# CW340_FTDI.net
KiCad netlist of a schematic drawn in Altium Designer
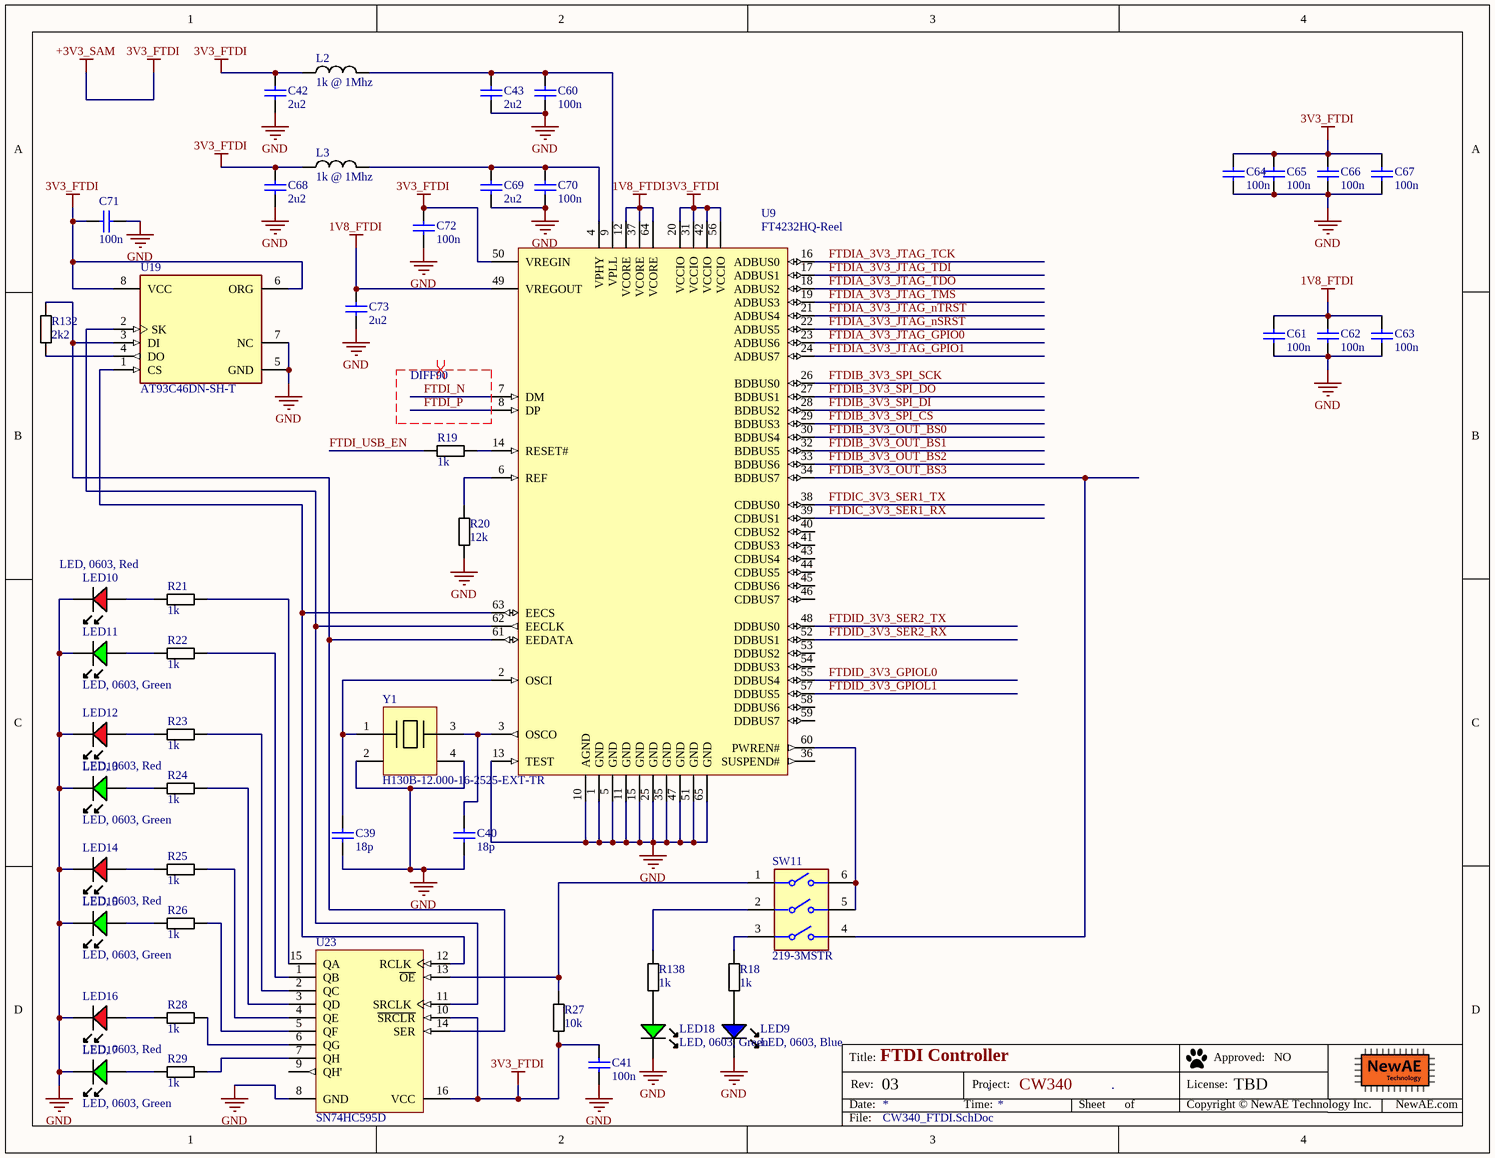
[diagram p0: CW340_FTDI.SchDoc]

(export (version "E")
  (design (tool "Eeschema 10.0.6"))
  (components
    (comp (ref "C39")
      (value "18p")
      (footprint "CAPC0402_M")
      (description "18p, 0402")
      (fields (field (name "PART NUMBER") "CCHIP-18p-0402"))
      (libsource (lib "NewAE_AltiumLib") (part "CAP"))
    )
    (comp (ref "C40")
      (value "18p")
      (footprint "CAPC0402_M")
      (description "18p, 0402")
      (fields (field (name "PART NUMBER") "CCHIP-18p-0402"))
      (libsource (lib "NewAE_AltiumLib") (part "CAP"))
    )
    (comp (ref "C41")
      (value "100n")
      (footprint "CAPC0402_M")
      (description "100n, 0402")
      (fields (field (name "PART NUMBER") "CCHIP-100n-0402"))
      (libsource (lib "NewAE_AltiumLib") (part "CAP"))
    )
    (comp (ref "C42")
      (value "2u2")
      (footprint "CAPC0603_M")
      (description "2u2, 0603")
      (fields (field (name "PART NUMBER") "CCHIP-2u2-0603"))
      (libsource (lib "NewAE_AltiumLib") (part "CAP"))
    )
    (comp (ref "C43")
      (value "2u2")
      (footprint "CAPC0603_M")
      (description "2u2, 0603")
      (fields (field (name "PART NUMBER") "CCHIP-2u2-0603"))
      (libsource (lib "NewAE_AltiumLib") (part "CAP"))
    )
    (comp (ref "C60")
      (value "100n")
      (footprint "CAPC0402_M")
      (description "100n, 0402")
      (fields (field (name "PART NUMBER") "CCHIP-100n-0402"))
      (libsource (lib "NewAE_AltiumLib") (part "CAP"))
    )
    (comp (ref "C61")
      (value "100n")
      (footprint "CAPC0402_M")
      (description "100n, 0402")
      (fields (field (name "PART NUMBER") "CCHIP-100n-0402"))
      (libsource (lib "NewAE_AltiumLib") (part "CAP"))
    )
    (comp (ref "C62")
      (value "100n")
      (footprint "CAPC0402_M")
      (description "100n, 0402")
      (fields (field (name "PART NUMBER") "CCHIP-100n-0402"))
      (libsource (lib "NewAE_AltiumLib") (part "CAP"))
    )
    (comp (ref "C63")
      (value "100n")
      (footprint "CAPC0402_M")
      (description "100n, 0402")
      (fields (field (name "PART NUMBER") "CCHIP-100n-0402"))
      (libsource (lib "NewAE_AltiumLib") (part "CAP"))
    )
    (comp (ref "C64")
      (value "100n")
      (footprint "CAPC0402_M")
      (description "100n, 0402")
      (fields (field (name "PART NUMBER") "CCHIP-100n-0402"))
      (libsource (lib "NewAE_AltiumLib") (part "CAP"))
    )
    (comp (ref "C65")
      (value "100n")
      (footprint "CAPC0402_M")
      (description "100n, 0402")
      (fields (field (name "PART NUMBER") "CCHIP-100n-0402"))
      (libsource (lib "NewAE_AltiumLib") (part "CAP"))
    )
    (comp (ref "C66")
      (value "100n")
      (footprint "CAPC0402_M")
      (description "100n, 0402")
      (fields (field (name "PART NUMBER") "CCHIP-100n-0402"))
      (libsource (lib "NewAE_AltiumLib") (part "CAP"))
    )
    (comp (ref "C67")
      (value "100n")
      (footprint "CAPC0402_M")
      (description "100n, 0402")
      (fields (field (name "PART NUMBER") "CCHIP-100n-0402"))
      (libsource (lib "NewAE_AltiumLib") (part "CAP"))
    )
    (comp (ref "C68")
      (value "2u2")
      (footprint "CAPC0603_M")
      (description "2u2, 0603")
      (fields (field (name "PART NUMBER") "CCHIP-2u2-0603"))
      (libsource (lib "NewAE_AltiumLib") (part "CAP"))
    )
    (comp (ref "C69")
      (value "2u2")
      (footprint "CAPC0603_M")
      (description "2u2, 0603")
      (fields (field (name "PART NUMBER") "CCHIP-2u2-0603"))
      (libsource (lib "NewAE_AltiumLib") (part "CAP"))
    )
    (comp (ref "C70")
      (value "100n")
      (footprint "CAPC0402_M")
      (description "100n, 0402")
      (fields (field (name "PART NUMBER") "CCHIP-100n-0402"))
      (libsource (lib "NewAE_AltiumLib") (part "CAP"))
    )
    (comp (ref "C71")
      (value "100n")
      (footprint "CAPC0402_M")
      (description "100n, 0402")
      (fields (field (name "PART NUMBER") "CCHIP-100n-0402"))
      (libsource (lib "NewAE_AltiumLib") (part "CAP"))
    )
    (comp (ref "C72")
      (value "100n")
      (footprint "CAPC0402_M")
      (description "100n, 0402")
      (fields (field (name "PART NUMBER") "CCHIP-100n-0402"))
      (libsource (lib "NewAE_AltiumLib") (part "CAP"))
    )
    (comp (ref "C73")
      (value "2u2")
      (footprint "CAPC0603_M")
      (description "2u2, 0603")
      (fields (field (name "PART NUMBER") "CCHIP-2u2-0603"))
      (libsource (lib "NewAE_AltiumLib") (part "CAP"))
    )
    (comp (ref "L2")
      (value "1k @ 1Mhz")
      (footprint "IND_0603")
      (description "Ferrite Beads HI CUR CHIP BD 0603 1000OHMS 25%")
      (fields (field (name "PART NUMBER") "FBCHIP-1k-0603"))
      (libsource (lib "NewAE_AltiumLib") (part "IND"))
    )
    (comp (ref "L3")
      (value "1k @ 1Mhz")
      (footprint "IND_0603")
      (description "Ferrite Beads HI CUR CHIP BD 0603 1000OHMS 25%")
      (fields (field (name "PART NUMBER") "FBCHIP-1k-0603"))
      (libsource (lib "NewAE_AltiumLib") (part "IND"))
    )
    (comp (ref "LED9")
      (value "LED, 0603, Blue")
      (footprint "LED-0603-BLUE")
      (description "Chip LED, Blue")
      (fields (field (name "PART NUMBER") "LEDCHIP_0603_BLUE"))
      (libsource (lib "NewAE_AltiumLib") (part "LED_BLUE"))
    )
    (comp (ref "LED10")
      (value "LED, 0603, Red")
      (footprint "LED-0603-RED")
      (description "Chip LED, Red")
      (fields (field (name "PART NUMBER") "LEDCHIP_0603_RED"))
      (libsource (lib "NewAE_AltiumLib") (part "LED_RED"))
    )
    (comp (ref "LED11")
      (value "LED, 0603, Green")
      (footprint "LED-0603-GREEN")
      (description "Chip LED, Green")
      (fields (field (name "PART NUMBER") "LEDCHIP_0603_GREEN"))
      (libsource (lib "NewAE_AltiumLib") (part "LED_GREEN"))
    )
    (comp (ref "LED12")
      (value "LED, 0603, Red")
      (footprint "LED-0603-RED")
      (description "Chip LED, Red")
      (fields (field (name "PART NUMBER") "LEDCHIP_0603_RED"))
      (libsource (lib "NewAE_AltiumLib") (part "LED_RED"))
    )
    (comp (ref "LED13")
      (value "LED, 0603, Green")
      (footprint "LED-0603-GREEN")
      (description "Chip LED, Green")
      (fields (field (name "PART NUMBER") "LEDCHIP_0603_GREEN"))
      (libsource (lib "NewAE_AltiumLib") (part "LED_GREEN"))
    )
    (comp (ref "LED14")
      (value "LED, 0603, Red")
      (footprint "LED-0603-RED")
      (description "Chip LED, Red")
      (fields (field (name "PART NUMBER") "LEDCHIP_0603_RED"))
      (libsource (lib "NewAE_AltiumLib") (part "LED_RED"))
    )
    (comp (ref "LED15")
      (value "LED, 0603, Green")
      (footprint "LED-0603-GREEN")
      (description "Chip LED, Green")
      (fields (field (name "PART NUMBER") "LEDCHIP_0603_GREEN"))
      (libsource (lib "NewAE_AltiumLib") (part "LED_GREEN"))
    )
    (comp (ref "LED16")
      (value "LED, 0603, Red")
      (footprint "LED-0603-RED")
      (description "Chip LED, Red")
      (fields (field (name "PART NUMBER") "LEDCHIP_0603_RED"))
      (libsource (lib "NewAE_AltiumLib") (part "LED_RED"))
    )
    (comp (ref "LED17")
      (value "LED, 0603, Green")
      (footprint "LED-0603-GREEN")
      (description "Chip LED, Green")
      (fields (field (name "PART NUMBER") "LEDCHIP_0603_GREEN"))
      (libsource (lib "NewAE_AltiumLib") (part "LED_GREEN"))
    )
    (comp (ref "LED18")
      (value "LED, 0603, Green")
      (footprint "LED-0603-GREEN")
      (description "Chip LED, Green")
      (fields (field (name "PART NUMBER") "LEDCHIP_0603_GREEN"))
      (libsource (lib "NewAE_AltiumLib") (part "LED_GREEN"))
    )
    (comp (ref "R18")
      (value "1k")
      (footprint "RESC1005X40N")
      (description "1k res, 0402, 1%, 1/16W")
      (fields (field (name "PART NUMBER") "RCHIP-1K-0402") (field (name "TOLERANCE") "1%"))
      (libsource (lib "") (part "RES-EU_1"))
    )
    (comp (ref "R19")
      (value "1k")
      (footprint "RESC1005X40N")
      (description "1k res, 0402, 1%, 1/16W")
      (fields (field (name "PART NUMBER") "RCHIP-1K-0402") (field (name "TOLERANCE") "1%"))
      (libsource (lib "NewAE_AltiumLib") (part "RES-EU"))
    )
    (comp (ref "R20")
      (value "12k")
      (footprint "RESC1608X55N")
      (description "12k res, 0603, 1%, 1/10W")
      (fields (field (name "PART NUMBER") "RCHIP-12K-0603") (field (name "TOLERANCE") "1%"))
      (libsource (lib "") (part "RES-EU_1"))
    )
    (comp (ref "R21")
      (value "1k")
      (footprint "RESC1005X40N")
      (description "1k res, 0402, 1%, 1/16W")
      (fields (field (name "PART NUMBER") "RCHIP-1K-0402") (field (name "TOLERANCE") "1%"))
      (libsource (lib "NewAE_AltiumLib") (part "RES-EU"))
    )
    (comp (ref "R22")
      (value "1k")
      (footprint "RESC1005X40N")
      (description "1k res, 0402, 1%, 1/16W")
      (fields (field (name "PART NUMBER") "RCHIP-1K-0402") (field (name "TOLERANCE") "1%"))
      (libsource (lib "NewAE_AltiumLib") (part "RES-EU"))
    )
    (comp (ref "R23")
      (value "1k")
      (footprint "RESC1005X40N")
      (description "1k res, 0402, 1%, 1/16W")
      (fields (field (name "PART NUMBER") "RCHIP-1K-0402") (field (name "TOLERANCE") "1%"))
      (libsource (lib "NewAE_AltiumLib") (part "RES-EU"))
    )
    (comp (ref "R24")
      (value "1k")
      (footprint "RESC1005X40N")
      (description "1k res, 0402, 1%, 1/16W")
      (fields (field (name "PART NUMBER") "RCHIP-1K-0402") (field (name "TOLERANCE") "1%"))
      (libsource (lib "NewAE_AltiumLib") (part "RES-EU"))
    )
    (comp (ref "R25")
      (value "1k")
      (footprint "RESC1005X40N")
      (description "1k res, 0402, 1%, 1/16W")
      (fields (field (name "PART NUMBER") "RCHIP-1K-0402") (field (name "TOLERANCE") "1%"))
      (libsource (lib "NewAE_AltiumLib") (part "RES-EU"))
    )
    (comp (ref "R26")
      (value "1k")
      (footprint "RESC1005X40N")
      (description "1k res, 0402, 1%, 1/16W")
      (fields (field (name "PART NUMBER") "RCHIP-1K-0402") (field (name "TOLERANCE") "1%"))
      (libsource (lib "NewAE_AltiumLib") (part "RES-EU"))
    )
    (comp (ref "R27")
      (value "10k")
      (footprint "RESC1005X40N")
      (description "10k res, 0402, 1%, 1/16W")
      (fields (field (name "PART NUMBER") "RCHIP-10K-0402") (field (name "TOLERANCE") "1%"))
      (libsource (lib "") (part "RES-EU_1"))
    )
    (comp (ref "R28")
      (value "1k")
      (footprint "RESC1005X40N")
      (description "1k res, 0402, 1%, 1/16W")
      (fields (field (name "PART NUMBER") "RCHIP-1K-0402") (field (name "TOLERANCE") "1%"))
      (libsource (lib "NewAE_AltiumLib") (part "RES-EU"))
    )
    (comp (ref "R29")
      (value "1k")
      (footprint "RESC1005X40N")
      (description "1k res, 0402, 1%, 1/16W")
      (fields (field (name "PART NUMBER") "RCHIP-1K-0402") (field (name "TOLERANCE") "1%"))
      (libsource (lib "NewAE_AltiumLib") (part "RES-EU"))
    )
    (comp (ref "R132")
      (value "2k2")
      (footprint "RESC1005X40N")
      (description "2k2 res, 0402, 1%, 1/16W")
      (fields (field (name "PART NUMBER") "RCHIP-2K2-0402") (field (name "TOLERANCE") "1%"))
      (libsource (lib "") (part "RES-EU_1"))
    )
    (comp (ref "R138")
      (value "1k")
      (footprint "RESC1005X40N")
      (description "1k res, 0402, 1%, 1/16W")
      (fields (field (name "PART NUMBER") "RCHIP-1K-0402") (field (name "TOLERANCE") "1%"))
      (libsource (lib "") (part "RES-EU_1"))
    )
    (comp (ref "SW11")
      (value "219-3MSTR")
      (footprint "FP-219-3MSTR-MFG")
      (description "SWITCH SLIDE DIP SPST 100MA 20V")
      (libsource (lib "Altium Content Vault") (part "7c490946f25aa2bb1cd4cef5bc3ec4e"))
    )
    (comp (ref "U9")
      (value "FT4232HQ-Reel")
      (footprint "QFN64_2_L")
      (description "Quad High Speed USB To Multipurpose UART/MPSSE IC, 64-pin QFN, Tape and Reel")
      (fields (field (name "MANUFACTURER") "FTDI"))
      (libsource (lib "Altium Content Vault") (part "COM-UART-FT4232H-QFN64"))
    )
    (comp (ref "U19")
      (value "AT93C46DN-SH-T")
      (footprint "FP-C04-057-SN-MFG")
      (description "IC EEPROM 1K SPI 2MHZ 8SOIC")
      (fields
        (field (name "MANUFACTURER") "Microchip")
        (field (name "OCTOPART") "https://octopart.com/at93c46dn-sh-t-microchip-77759177")
      )
      (libsource (lib "Altium Content Vault") (part "8bb9afc094b350e480db350c7247e52"))
    )
    (comp (ref "U23")
      (value "SN74HC595D")
      (footprint "D0016A_L")
      (description "8-Bit Shift Registers With 3-State Output Registers, D0016A, TUBE")
      (fields
        (field (name "GENERIC PART NUMBER") "SN74HC595")
        (field (name "MANUFACTURER") "Texas Instruments")
      )
      (libsource (lib "Altium Content Vault") (part "TI-SN74XHCT595X_SN74LV595A-16"))
    )
    (comp (ref "Y1")
      (value "H130B-12.000-16-2525-EXT-TR")
      (footprint "5x3.2MM XTAL")
      (description "12MHz ±25ppm Crystal 16pF 35 Ohms 4-SMD, No Lead")
      (fields (field (name "MANUFACTURER PART NUMBER") "H130B-12.000-16-2525-EXT-TR"))
      (libsource (lib "NewAE_AltiumLib") (part "H130B-12.000-16-2525-EXT-TR"))
    )
  )
  (nets
    (net (code "1") (name "+3V3_SAM") (class "Default")
      (node (ref "C41") (pin "1") (pinfunction "1_1") (pintype "passive"))
      (node (ref "C42") (pin "1") (pinfunction "1_1") (pintype "passive"))
      (node (ref "C64") (pin "1") (pinfunction "1_1") (pintype "passive"))
      (node (ref "C65") (pin "1") (pinfunction "1_1") (pintype "passive"))
      (node (ref "C66") (pin "1") (pinfunction "1_1") (pintype "passive"))
      (node (ref "C67") (pin "1") (pinfunction "1_1") (pintype "passive"))
      (node (ref "C68") (pin "1") (pinfunction "1_1") (pintype "passive"))
      (node (ref "C71") (pin "1") (pinfunction "1_1") (pintype "passive"))
      (node (ref "C72") (pin "1") (pinfunction "1_1") (pintype "passive"))
      (node (ref "L2") (pin "1") (pinfunction "1_1") (pintype "passive"))
      (node (ref "L3") (pin "1") (pinfunction "1_1") (pintype "passive"))
      (node (ref "R27") (pin "2") (pinfunction "2_2") (pintype "passive"))
      (node (ref "U19") (pin "6") (pinfunction "ORG_6") (pintype "passive"))
      (node (ref "U19") (pin "8") (pinfunction "VCC_8") (pintype "power_in"))
      (node (ref "U23") (pin "10") (pinfunction "~{SRCLR}_10") (pintype "input"))
      (node (ref "U23") (pin "16") (pinfunction "VCC_16") (pintype "power_in"))
      (node (ref "U9") (pin "20") (pinfunction "VCCIO_20") (pintype "power_in"))
      (node (ref "U9") (pin "31") (pinfunction "VCCIO_31") (pintype "power_in"))
      (node (ref "U9") (pin "42") (pinfunction "VCCIO_42") (pintype "power_in"))
      (node (ref "U9") (pin "50") (pinfunction "VREGIN_50") (pintype "power_in"))
      (node (ref "U9") (pin "56") (pinfunction "VCCIO_56") (pintype "power_in"))
    )
    (net (code "2") (name "/FTDIA_3V3_JTAG_GPIO0") (class "Default")
      (node (ref "U9") (pin "23") (pinfunction "ADBUS6_23") (pintype "bidirectional"))
    )
    (net (code "3") (name "/FTDIA_3V3_JTAG_GPIO1") (class "Default")
      (node (ref "U9") (pin "24") (pinfunction "ADBUS7_24") (pintype "bidirectional"))
    )
    (net (code "4") (name "/FTDIA_3V3_JTAG_TCK") (class "Default")
      (node (ref "U9") (pin "16") (pinfunction "ADBUS0_16") (pintype "bidirectional"))
    )
    (net (code "5") (name "/FTDIA_3V3_JTAG_TDI") (class "Default")
      (node (ref "U9") (pin "17") (pinfunction "ADBUS1_17") (pintype "bidirectional"))
    )
    (net (code "6") (name "/FTDIA_3V3_JTAG_TDO") (class "Default")
      (node (ref "U9") (pin "18") (pinfunction "ADBUS2_18") (pintype "bidirectional"))
    )
    (net (code "7") (name "/FTDIA_3V3_JTAG_TMS") (class "Default")
      (node (ref "U9") (pin "19") (pinfunction "ADBUS3_19") (pintype "bidirectional"))
    )
    (net (code "8") (name "/FTDIA_3V3_JTAG_nSRST") (class "Default")
      (node (ref "U9") (pin "22") (pinfunction "ADBUS5_22") (pintype "bidirectional"))
    )
    (net (code "9") (name "/FTDIA_3V3_JTAG_nTRST") (class "Default")
      (node (ref "U9") (pin "21") (pinfunction "ADBUS4_21") (pintype "bidirectional"))
    )
    (net (code "10") (name "/FTDIB_3V3_OUT_BS0") (class "Default")
      (node (ref "U9") (pin "30") (pinfunction "BDBUS4_30") (pintype "bidirectional"))
    )
    (net (code "11") (name "/FTDIB_3V3_OUT_BS1") (class "Default")
      (node (ref "U9") (pin "32") (pinfunction "BDBUS5_32") (pintype "bidirectional"))
    )
    (net (code "12") (name "/FTDIB_3V3_OUT_BS2") (class "Default")
      (node (ref "U9") (pin "33") (pinfunction "BDBUS6_33") (pintype "bidirectional"))
    )
    (net (code "13") (name "/FTDIB_3V3_OUT_BS3") (class "Default")
      (node (ref "SW11") (pin "4") (pinfunction "4_4") (pintype "passive"))
      (node (ref "U9") (pin "34") (pinfunction "BDBUS7_34") (pintype "bidirectional"))
    )
    (net (code "14") (name "/FTDIB_3V3_SPI_CS") (class "Default")
      (node (ref "U9") (pin "29") (pinfunction "BDBUS3_29") (pintype "bidirectional"))
    )
    (net (code "15") (name "/FTDIB_3V3_SPI_DI") (class "Default")
      (node (ref "U9") (pin "28") (pinfunction "BDBUS2_28") (pintype "bidirectional"))
    )
    (net (code "16") (name "/FTDIB_3V3_SPI_DO") (class "Default")
      (node (ref "U9") (pin "27") (pinfunction "BDBUS1_27") (pintype "bidirectional"))
    )
    (net (code "17") (name "/FTDIB_3V3_SPI_SCK") (class "Default")
      (node (ref "U9") (pin "26") (pinfunction "BDBUS0_26") (pintype "bidirectional"))
    )
    (net (code "18") (name "/FTDIC_3V3_SER1_RX") (class "Default")
      (node (ref "U9") (pin "39") (pinfunction "CDBUS1_39") (pintype "bidirectional"))
    )
    (net (code "19") (name "/FTDIC_3V3_SER1_TX") (class "Default")
      (node (ref "U9") (pin "38") (pinfunction "CDBUS0_38") (pintype "bidirectional"))
    )
    (net (code "20") (name "/FTDID_3V3_GPIOL0") (class "Default")
      (node (ref "U9") (pin "55") (pinfunction "DDBUS4_55") (pintype "bidirectional"))
    )
    (net (code "21") (name "/FTDID_3V3_GPIOL1") (class "Default")
      (node (ref "U9") (pin "57") (pinfunction "DDBUS5_57") (pintype "bidirectional"))
    )
    (net (code "22") (name "/FTDID_3V3_SER2_RX") (class "Default")
      (node (ref "U9") (pin "52") (pinfunction "DDBUS1_52") (pintype "bidirectional"))
    )
    (net (code "23") (name "/FTDID_3V3_SER2_TX") (class "Default")
      (node (ref "U9") (pin "48") (pinfunction "DDBUS0_48") (pintype "bidirectional"))
    )
    (net (code "24") (name "/FTDI_N") (class "Default")
      (node (ref "U9") (pin "7") (pinfunction "DM_7") (pintype "input"))
    )
    (net (code "25") (name "/FTDI_P") (class "Default")
      (node (ref "U9") (pin "8") (pinfunction "DP_8") (pintype "input"))
    )
    (net (code "26") (name "/FTDI_USB_EN") (class "Default")
      (node (ref "R19") (pin "2") (pinfunction "2_2") (pintype "passive"))
    )
    (net (code "27") (name "1V8_FTDI") (class "Default")
      (node (ref "C61") (pin "1") (pinfunction "1_1") (pintype "passive"))
      (node (ref "C62") (pin "1") (pinfunction "1_1") (pintype "passive"))
      (node (ref "C63") (pin "1") (pinfunction "1_1") (pintype "passive"))
      (node (ref "C73") (pin "1") (pinfunction "1_1") (pintype "passive"))
      (node (ref "U9") (pin "12") (pinfunction "VCORE_12") (pintype "power_in"))
      (node (ref "U9") (pin "37") (pinfunction "VCORE_37") (pintype "power_in"))
      (node (ref "U9") (pin "49") (pinfunction "VREGOUT_49") (pintype "power_in"))
      (node (ref "U9") (pin "64") (pinfunction "VCORE_64") (pintype "power_in"))
    )
    (net (code "28") (name "GND") (class "Default")
      (node (ref "C39") (pin "2") (pinfunction "2_2") (pintype "passive"))
      (node (ref "C40") (pin "2") (pinfunction "2_2") (pintype "passive"))
      (node (ref "C41") (pin "2") (pinfunction "2_2") (pintype "passive"))
      (node (ref "C42") (pin "2") (pinfunction "2_2") (pintype "passive"))
      (node (ref "C43") (pin "2") (pinfunction "2_2") (pintype "passive"))
      (node (ref "C60") (pin "2") (pinfunction "2_2") (pintype "passive"))
      (node (ref "C61") (pin "2") (pinfunction "2_2") (pintype "passive"))
      (node (ref "C62") (pin "2") (pinfunction "2_2") (pintype "passive"))
      (node (ref "C63") (pin "2") (pinfunction "2_2") (pintype "passive"))
      (node (ref "C64") (pin "2") (pinfunction "2_2") (pintype "passive"))
      (node (ref "C65") (pin "2") (pinfunction "2_2") (pintype "passive"))
      (node (ref "C66") (pin "2") (pinfunction "2_2") (pintype "passive"))
      (node (ref "C67") (pin "2") (pinfunction "2_2") (pintype "passive"))
      (node (ref "C68") (pin "2") (pinfunction "2_2") (pintype "passive"))
      (node (ref "C69") (pin "2") (pinfunction "2_2") (pintype "passive"))
      (node (ref "C70") (pin "2") (pinfunction "2_2") (pintype "passive"))
      (node (ref "C71") (pin "2") (pinfunction "2_2") (pintype "passive"))
      (node (ref "C72") (pin "2") (pinfunction "2_2") (pintype "passive"))
      (node (ref "C73") (pin "2") (pinfunction "2_2") (pintype "passive"))
      (node (ref "LED10") (pin "K") (pinfunction "K_K") (pintype "passive"))
      (node (ref "LED11") (pin "K") (pinfunction "K_K") (pintype "passive"))
      (node (ref "LED12") (pin "K") (pinfunction "K_K") (pintype "passive"))
      (node (ref "LED13") (pin "K") (pinfunction "K_K") (pintype "passive"))
      (node (ref "LED14") (pin "K") (pinfunction "K_K") (pintype "passive"))
      (node (ref "LED15") (pin "K") (pinfunction "K_K") (pintype "passive"))
      (node (ref "LED16") (pin "K") (pinfunction "K_K") (pintype "passive"))
      (node (ref "LED17") (pin "K") (pinfunction "K_K") (pintype "passive"))
      (node (ref "LED18") (pin "K") (pinfunction "K_K") (pintype "passive"))
      (node (ref "LED9") (pin "K") (pinfunction "K_K") (pintype "passive"))
      (node (ref "R20") (pin "2") (pinfunction "2_2") (pintype "passive"))
      (node (ref "U19") (pin "5") (pinfunction "GND_5") (pintype "power_in"))
      (node (ref "U19") (pin "7") (pinfunction "NC_7") (pintype "passive"))
      (node (ref "U23") (pin "8") (pinfunction "GND_8") (pintype "power_in"))
      (node (ref "U9") (pin "1") (pinfunction "GND_1") (pintype "power_in"))
      (node (ref "U9") (pin "10") (pinfunction "AGND_10") (pintype "power_in"))
      (node (ref "U9") (pin "11") (pinfunction "GND_11") (pintype "power_in"))
      (node (ref "U9") (pin "13") (pinfunction "TEST_13") (pintype "input"))
      (node (ref "U9") (pin "15") (pinfunction "GND_15") (pintype "power_in"))
      (node (ref "U9") (pin "25") (pinfunction "GND_25") (pintype "power_in"))
      (node (ref "U9") (pin "35") (pinfunction "GND_35") (pintype "power_in"))
      (node (ref "U9") (pin "47") (pinfunction "GND_47") (pintype "power_in"))
      (node (ref "U9") (pin "5") (pinfunction "GND_5") (pintype "power_in"))
      (node (ref "U9") (pin "51") (pinfunction "GND_51") (pintype "power_in"))
      (node (ref "U9") (pin "65") (pinfunction "GND_65") (pintype "power_in"))
      (node (ref "Y1") (pin "2") (pinfunction "2_2") (pintype "passive"))
      (node (ref "Y1") (pin "4") (pinfunction "4_4") (pintype "passive"))
    )
    (net (code "29") (name "Net-(LED9-PadA)") (class "Default")
      (node (ref "LED9") (pin "A") (pinfunction "A_A") (pintype "passive"))
      (node (ref "R18") (pin "2") (pinfunction "2_2") (pintype "passive"))
    )
    (net (code "30") (name "Net-(LED10-PadA)") (class "Default")
      (node (ref "LED10") (pin "A") (pinfunction "A_A") (pintype "passive"))
      (node (ref "R21") (pin "2") (pinfunction "2_2") (pintype "passive"))
    )
    (net (code "31") (name "Net-(LED11-PadA)") (class "Default")
      (node (ref "LED11") (pin "A") (pinfunction "A_A") (pintype "passive"))
      (node (ref "R22") (pin "2") (pinfunction "2_2") (pintype "passive"))
    )
    (net (code "32") (name "Net-(LED12-PadA)") (class "Default")
      (node (ref "LED12") (pin "A") (pinfunction "A_A") (pintype "passive"))
      (node (ref "R23") (pin "2") (pinfunction "2_2") (pintype "passive"))
    )
    (net (code "33") (name "Net-(LED13-PadA)") (class "Default")
      (node (ref "LED13") (pin "A") (pinfunction "A_A") (pintype "passive"))
      (node (ref "R24") (pin "2") (pinfunction "2_2") (pintype "passive"))
    )
    (net (code "34") (name "Net-(LED14-PadA)") (class "Default")
      (node (ref "LED14") (pin "A") (pinfunction "A_A") (pintype "passive"))
      (node (ref "R25") (pin "2") (pinfunction "2_2") (pintype "passive"))
    )
    (net (code "35") (name "Net-(LED15-PadA)") (class "Default")
      (node (ref "LED15") (pin "A") (pinfunction "A_A") (pintype "passive"))
      (node (ref "R26") (pin "2") (pinfunction "2_2") (pintype "passive"))
    )
    (net (code "36") (name "Net-(LED16-PadA)") (class "Default")
      (node (ref "LED16") (pin "A") (pinfunction "A_A") (pintype "passive"))
      (node (ref "R28") (pin "2") (pinfunction "2_2") (pintype "passive"))
    )
    (net (code "37") (name "Net-(LED17-PadA)") (class "Default")
      (node (ref "LED17") (pin "A") (pinfunction "A_A") (pintype "passive"))
      (node (ref "R29") (pin "2") (pinfunction "2_2") (pintype "passive"))
    )
    (net (code "38") (name "Net-(LED18-PadA)") (class "Default")
      (node (ref "LED18") (pin "A") (pinfunction "A_A") (pintype "passive"))
      (node (ref "R138") (pin "2") (pinfunction "2_2") (pintype "passive"))
    )
    (net (code "39") (name "Net-(R18-Pad1)") (class "Default")
      (node (ref "R18") (pin "1") (pinfunction "1_1") (pintype "passive"))
      (node (ref "SW11") (pin "3") (pinfunction "3_3") (pintype "passive"))
    )
    (net (code "40") (name "Net-(R138-Pad1)") (class "Default")
      (node (ref "R138") (pin "1") (pinfunction "1_1") (pintype "passive"))
      (node (ref "SW11") (pin "2") (pinfunction "2_2") (pintype "passive"))
    )
    (net (code "41") (name "Net-(U9-OSCI)") (class "Default")
      (node (ref "C39") (pin "1") (pinfunction "1_1") (pintype "passive"))
      (node (ref "U9") (pin "2") (pinfunction "OSCI_2") (pintype "input"))
      (node (ref "Y1") (pin "1") (pinfunction "1_1") (pintype "passive"))
    )
    (net (code "42") (name "Net-(U9-OSCO)") (class "Default")
      (node (ref "C40") (pin "1") (pinfunction "1_1") (pintype "passive"))
      (node (ref "U9") (pin "3") (pinfunction "OSCO_3") (pintype "output"))
      (node (ref "Y1") (pin "3") (pinfunction "3_3") (pintype "passive"))
    )
    (net (code "43") (name "Net-(U9-PWREN#)") (class "Default")
      (node (ref "SW11") (pin "5") (pinfunction "5_5") (pintype "passive"))
      (node (ref "SW11") (pin "6") (pinfunction "6_6") (pintype "passive"))
      (node (ref "U9") (pin "60") (pinfunction "PWREN#_60") (pintype "output"))
    )
    (net (code "44") (name "Net-(U9-REF)") (class "Default")
      (node (ref "R20") (pin "1") (pinfunction "1_1") (pintype "passive"))
      (node (ref "U9") (pin "6") (pinfunction "REF_6") (pintype "input"))
    )
    (net (code "45") (name "Net-(U9-RESET#)") (class "Default")
      (node (ref "R19") (pin "1") (pinfunction "1_1") (pintype "passive"))
      (node (ref "U9") (pin "14") (pinfunction "RESET#_14") (pintype "input"))
    )
    (net (code "46") (name "Net-(U9-VPHY)") (class "Default")
      (node (ref "C69") (pin "1") (pinfunction "1_1") (pintype "passive"))
      (node (ref "C70") (pin "1") (pinfunction "1_1") (pintype "passive"))
      (node (ref "L3") (pin "2") (pinfunction "2_2") (pintype "passive"))
      (node (ref "U9") (pin "4") (pinfunction "VPHY_4") (pintype "power_in"))
    )
    (net (code "47") (name "Net-(U9-VPLL)") (class "Default")
      (node (ref "C43") (pin "1") (pinfunction "1_1") (pintype "passive"))
      (node (ref "C60") (pin "1") (pinfunction "1_1") (pintype "passive"))
      (node (ref "L2") (pin "2") (pinfunction "2_2") (pintype "passive"))
      (node (ref "U9") (pin "9") (pinfunction "VPLL_9") (pintype "power_in"))
    )
    (net (code "48") (name "Net-(U19-CS)") (class "Default")
      (node (ref "U19") (pin "1") (pinfunction "CS_1") (pintype "input"))
      (node (ref "U23") (pin "12") (pinfunction "RCLK_12") (pintype "input"))
      (node (ref "U9") (pin "63") (pinfunction "EECS_63") (pintype "bidirectional"))
    )
    (net (code "49") (name "Net-(U19-DI)") (class "Default")
      (node (ref "R132") (pin "1") (pinfunction "1_1") (pintype "passive"))
      (node (ref "U19") (pin "3") (pinfunction "DI_3") (pintype "input"))
      (node (ref "U23") (pin "14") (pinfunction "SER_14") (pintype "input"))
      (node (ref "U9") (pin "61") (pinfunction "EEDATA_61") (pintype "bidirectional"))
    )
    (net (code "50") (name "Net-(U19-DO)") (class "Default")
      (node (ref "R132") (pin "2") (pinfunction "2_2") (pintype "passive"))
      (node (ref "U19") (pin "4") (pinfunction "DO_4") (pintype "output"))
    )
    (net (code "51") (name "Net-(U19-SK)") (class "Default")
      (node (ref "U19") (pin "2") (pinfunction "SK_2") (pintype "input"))
      (node (ref "U23") (pin "11") (pinfunction "SRCLK_11") (pintype "input"))
      (node (ref "U9") (pin "62") (pinfunction "EECLK_62") (pintype "output"))
    )
    (net (code "52") (name "Net-(U23-QA)") (class "Default")
      (node (ref "R21") (pin "1") (pinfunction "1_1") (pintype "passive"))
      (node (ref "U23") (pin "15") (pinfunction "QA_15") (pintype "tri_state"))
    )
    (net (code "53") (name "Net-(U23-QB)") (class "Default")
      (node (ref "R22") (pin "1") (pinfunction "1_1") (pintype "passive"))
      (node (ref "U23") (pin "1") (pinfunction "QB_1") (pintype "tri_state"))
    )
    (net (code "54") (name "Net-(U23-QC)") (class "Default")
      (node (ref "R23") (pin "1") (pinfunction "1_1") (pintype "passive"))
      (node (ref "U23") (pin "2") (pinfunction "QC_2") (pintype "tri_state"))
    )
    (net (code "55") (name "Net-(U23-QD)") (class "Default")
      (node (ref "R24") (pin "1") (pinfunction "1_1") (pintype "passive"))
      (node (ref "U23") (pin "3") (pinfunction "QD_3") (pintype "tri_state"))
    )
    (net (code "56") (name "Net-(U23-QE)") (class "Default")
      (node (ref "R25") (pin "1") (pinfunction "1_1") (pintype "passive"))
      (node (ref "U23") (pin "4") (pinfunction "QE_4") (pintype "tri_state"))
    )
    (net (code "57") (name "Net-(U23-QF)") (class "Default")
      (node (ref "R26") (pin "1") (pinfunction "1_1") (pintype "passive"))
      (node (ref "U23") (pin "5") (pinfunction "QF_5") (pintype "tri_state"))
    )
    (net (code "58") (name "Net-(U23-QG)") (class "Default")
      (node (ref "R28") (pin "1") (pinfunction "1_1") (pintype "passive"))
      (node (ref "U23") (pin "6") (pinfunction "QG_6") (pintype "tri_state"))
    )
    (net (code "59") (name "Net-(U23-QH)") (class "Default")
      (node (ref "R29") (pin "1") (pinfunction "1_1") (pintype "passive"))
      (node (ref "U23") (pin "7") (pinfunction "QH_7") (pintype "tri_state"))
    )
    (net (code "60") (name "Net-(U23-~{OE})") (class "Default")
      (node (ref "R27") (pin "1") (pinfunction "1_1") (pintype "passive"))
      (node (ref "SW11") (pin "1") (pinfunction "1_1") (pintype "passive"))
      (node (ref "U23") (pin "13") (pinfunction "~{OE}_13") (pintype "input"))
    )
    (net (code "61") (name "unconnected-(U9-CDBUS2-Pad40)") (class "Default")
      (node (ref "U9") (pin "40") (pinfunction "CDBUS2_40") (pintype "bidirectional"))
    )
    (net (code "62") (name "unconnected-(U9-CDBUS3-Pad41)") (class "Default")
      (node (ref "U9") (pin "41") (pinfunction "CDBUS3_41") (pintype "bidirectional"))
    )
    (net (code "63") (name "unconnected-(U9-CDBUS4-Pad43)") (class "Default")
      (node (ref "U9") (pin "43") (pinfunction "CDBUS4_43") (pintype "bidirectional"))
    )
    (net (code "64") (name "unconnected-(U9-CDBUS5-Pad44)") (class "Default")
      (node (ref "U9") (pin "44") (pinfunction "CDBUS5_44") (pintype "bidirectional"))
    )
    (net (code "65") (name "unconnected-(U9-CDBUS6-Pad45)") (class "Default")
      (node (ref "U9") (pin "45") (pinfunction "CDBUS6_45") (pintype "bidirectional"))
    )
    (net (code "66") (name "unconnected-(U9-CDBUS7-Pad46)") (class "Default")
      (node (ref "U9") (pin "46") (pinfunction "CDBUS7_46") (pintype "bidirectional"))
    )
    (net (code "67") (name "unconnected-(U9-DDBUS2-Pad53)") (class "Default")
      (node (ref "U9") (pin "53") (pinfunction "DDBUS2_53") (pintype "bidirectional"))
    )
    (net (code "68") (name "unconnected-(U9-DDBUS3-Pad54)") (class "Default")
      (node (ref "U9") (pin "54") (pinfunction "DDBUS3_54") (pintype "bidirectional"))
    )
    (net (code "69") (name "unconnected-(U9-DDBUS6-Pad58)") (class "Default")
      (node (ref "U9") (pin "58") (pinfunction "DDBUS6_58") (pintype "bidirectional"))
    )
    (net (code "70") (name "unconnected-(U9-DDBUS7-Pad59)") (class "Default")
      (node (ref "U9") (pin "59") (pinfunction "DDBUS7_59") (pintype "bidirectional"))
    )
    (net (code "71") (name "unconnected-(U9-SUSPEND#-Pad36)") (class "Default")
      (node (ref "U9") (pin "36") (pinfunction "SUSPEND#_36") (pintype "output"))
    )
    (net (code "72") (name "unconnected-(U23-QH'-Pad9)") (class "Default")
      (node (ref "U23") (pin "9") (pinfunction "QH'_9") (pintype "output"))
    )
  )
)
